# Light.net
KiCad netlist of a schematic drawn in Altium Designer
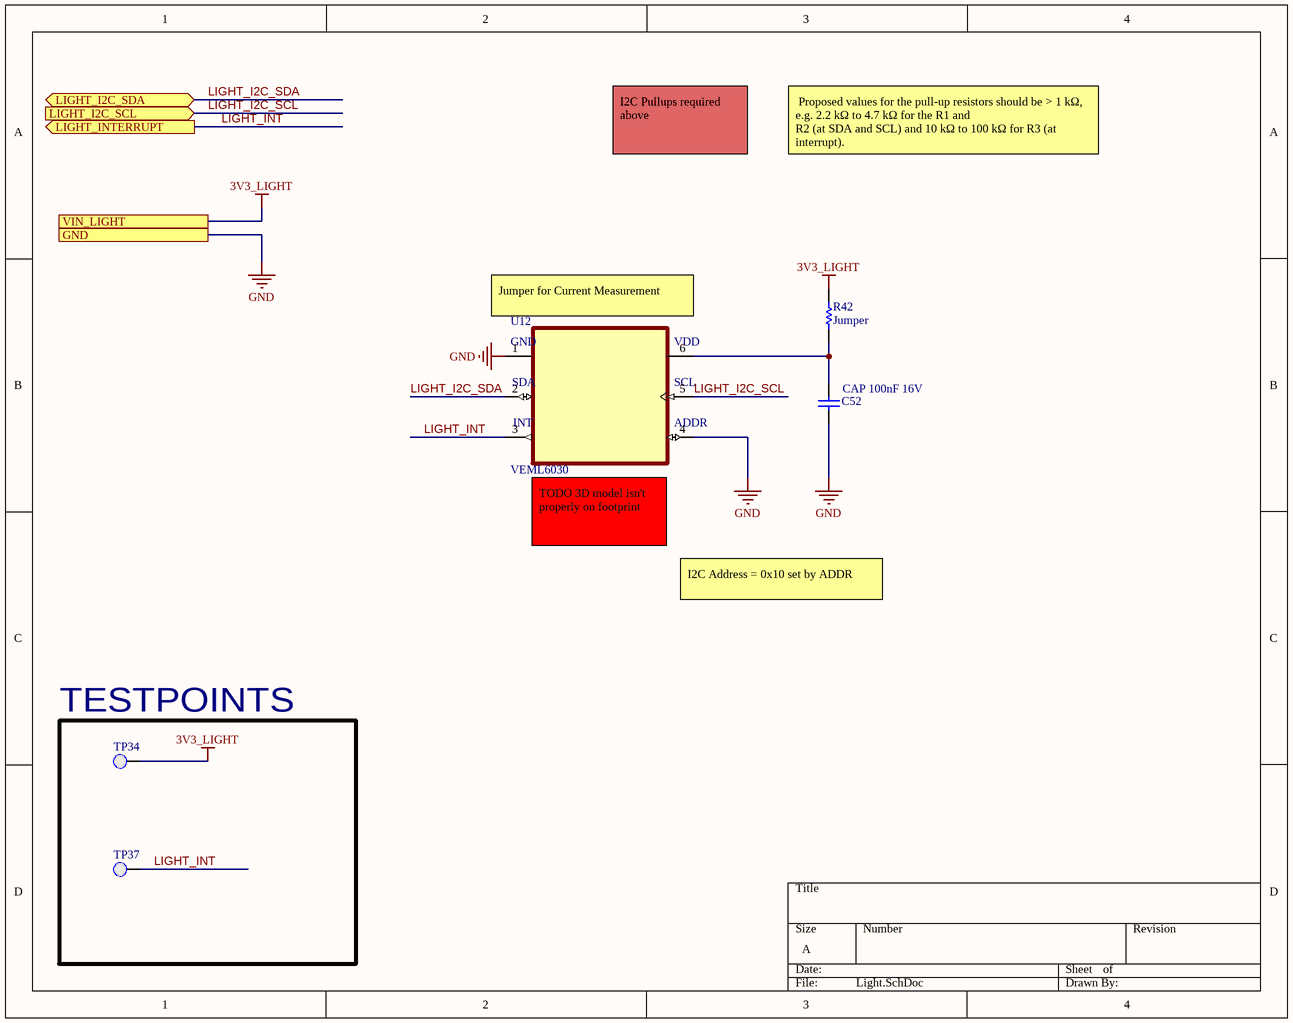
[diagram p0: Light.SchDoc]

(export (version "E")
  (design (tool "Eeschema 10.0.6"))
  (components
    (comp (ref "C52")
      (value "CAP 100nF 16V")
      (footprint "CAPC0402(1005)60_M")
      (description "CAP 100nF 16V ±10% 0402 (1005 Metric) Thickness 0.6mm SMD")
      (fields (field (name "TOLERANCE") "Â±10%"))
      (libsource (lib "Altium Content Vault") (part "CAP"))
    )
    (comp (ref "R42")
      (value "Jumper")
      (footprint "RESC0805(2012)_N")
      (description "Jumper 0805 (2012 Metric)")
      (fields (field (name "TOLERANCE") "None"))
      (libsource (lib "Altium Content Vault") (part "RES"))
    )
    (comp (ref "TP34")
      (value "0.1\" Pad")
      (footprint "PCBComponent")
      (libsource (lib "Components - 12.02.20 - 18.05") (part "0.1{dblquote} Pad-A.4"))
    )
    (comp (ref "TP37")
      (value "0.1\" Pad")
      (footprint "PCBComponent")
      (libsource (lib "Components - 12.02.20 - 18.05") (part "0.1{dblquote} Pad-A.4"))
    )
    (comp (ref "U12")
      (value "VEML6030")
      (footprint "SnapEDApcb:VISHAY_VEML6030_2X2X0.87")
      (description "Optical Sensor Ambient 550nm IÂ²C 6-SMD, No Lead")
      (fields (field (name "MF") "Vishay"))
      (libsource (lib "SnapEDAsch") (part "VEML6030"))
    )
  )
  (nets
    (net (code "1") (name "/LIGHT_I2C_SCL") (class "Default")
      (node (ref "U12") (pin "5") (pinfunction "SCL_5") (pintype "input"))
    )
    (net (code "2") (name "/LIGHT_I2C_SDA") (class "Default")
      (node (ref "U12") (pin "2") (pinfunction "SDA_2") (pintype "bidirectional"))
    )
    (net (code "3") (name "/LIGHT_INT") (class "Default")
      (node (ref "TP37") (pin "1") (pinfunction "PAD_1") (pintype "passive"))
      (node (ref "U12") (pin "3") (pinfunction "INT_3") (pintype "output"))
    )
    (net (code "4") (name "3V3_LIGHT") (class "Default")
      (node (ref "R42") (pin "1") (pinfunction "1_1") (pintype "passive"))
      (node (ref "TP34") (pin "1") (pinfunction "PAD_1") (pintype "passive"))
    )
    (net (code "5") (name "GND") (class "Default")
      (node (ref "C52") (pin "1") (pinfunction "1_1") (pintype "passive"))
      (node (ref "U12") (pin "1") (pinfunction "GND_1") (pintype "power_in"))
      (node (ref "U12") (pin "4") (pinfunction "ADDR_4") (pintype "bidirectional"))
    )
    (net (code "6") (name "Net-(U12-VDD)") (class "Default")
      (node (ref "C52") (pin "2") (pinfunction "2_2") (pintype "passive"))
      (node (ref "R42") (pin "2") (pinfunction "2_2") (pintype "passive"))
      (node (ref "U12") (pin "6") (pinfunction "VDD_6") (pintype "power_in"))
    )
  )
)
